# M633.net
KiCad netlist of a schematic drawn in EAGLE
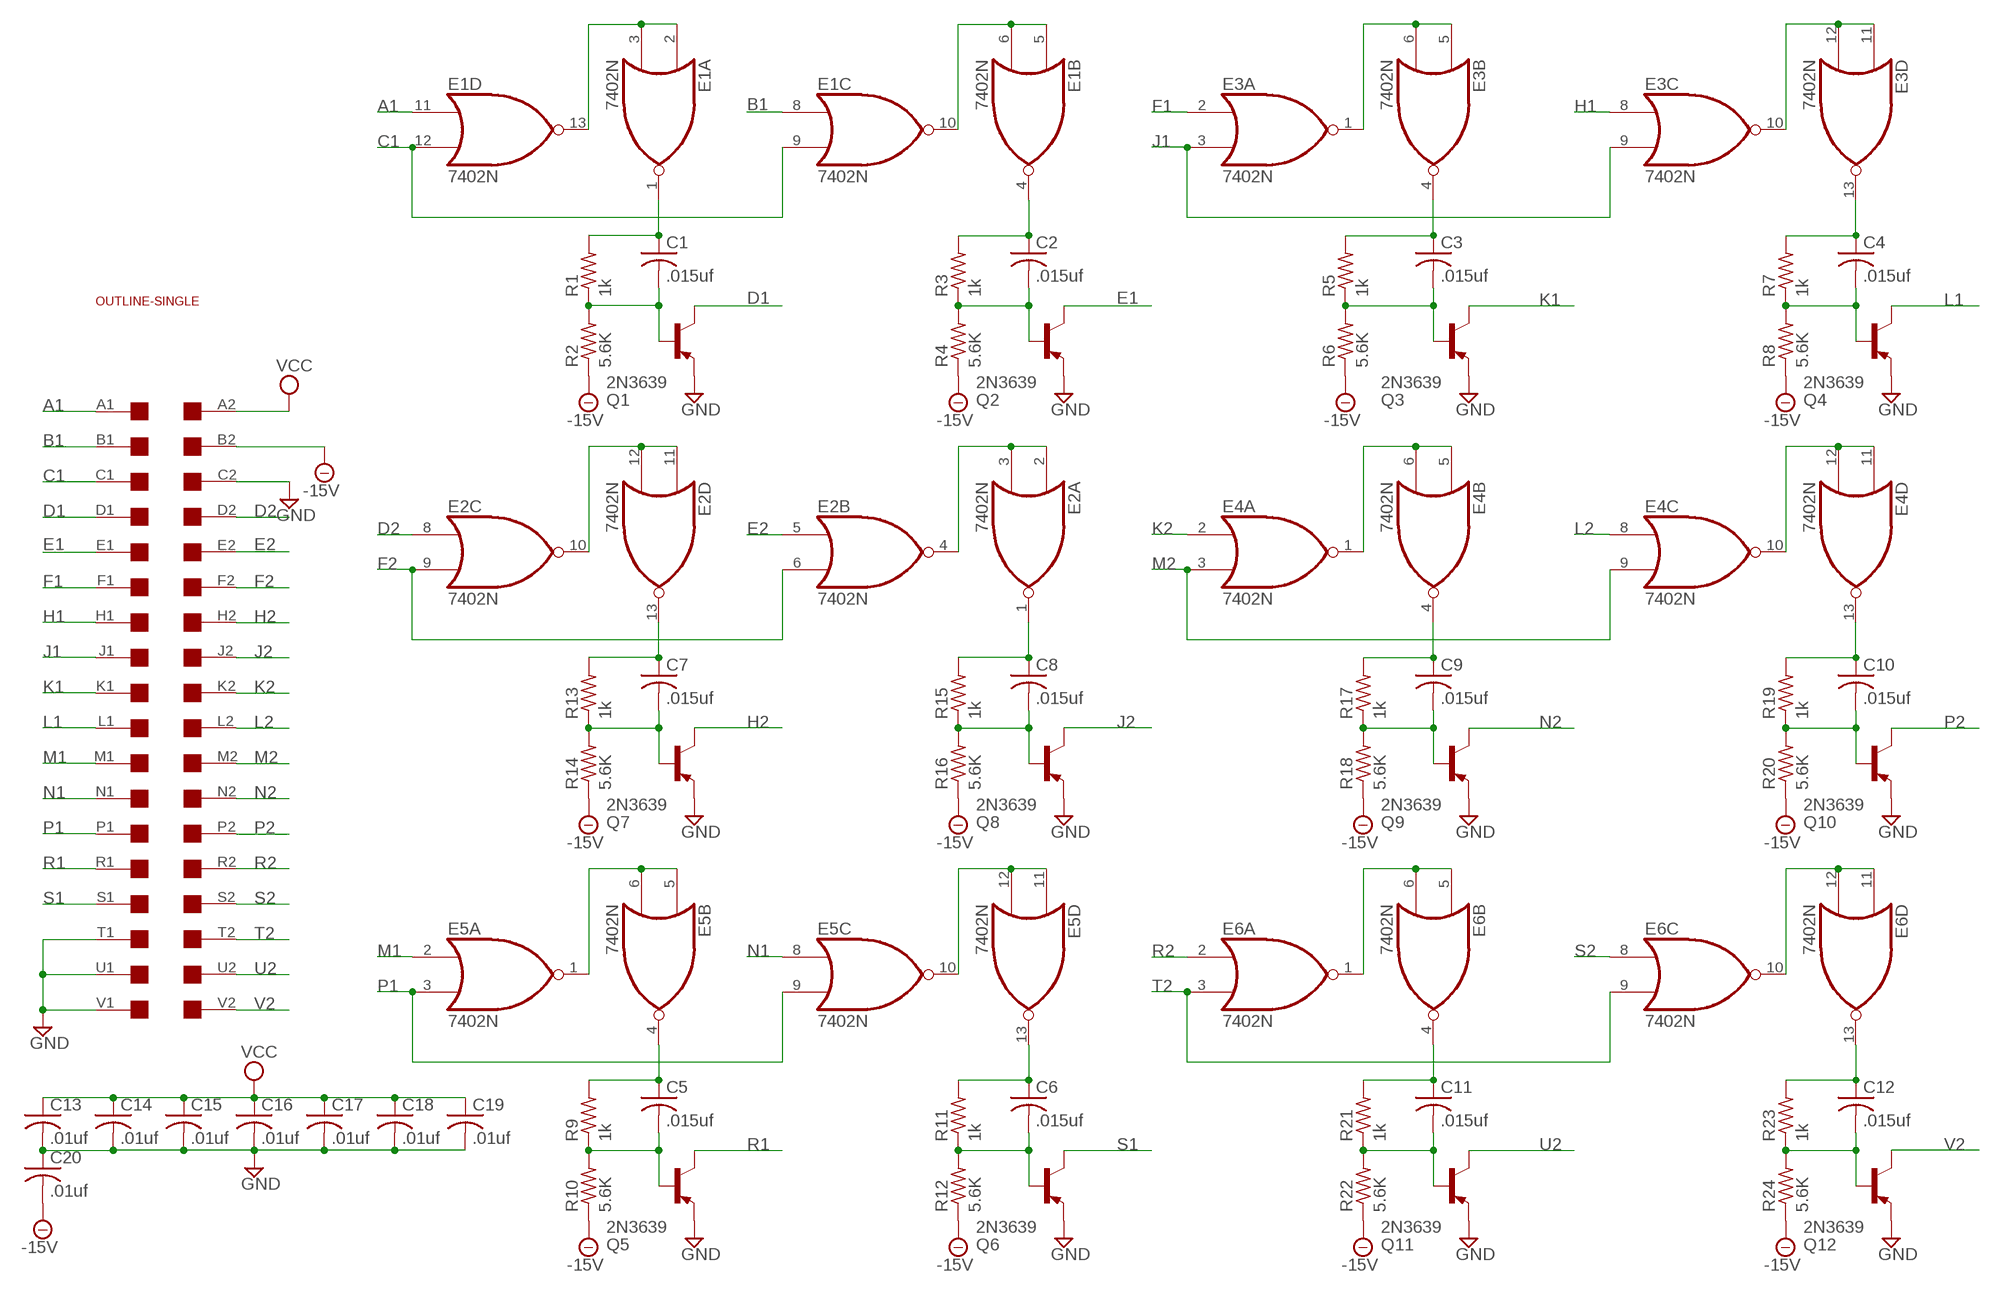
[diagram p0: schematic, sheet 1]

(export (version "E")
  (design (tool "Eeschema 10.0.6"))
  (components
    (comp (ref "C1")
      (value ".015uf")
      (footprint "eagle-import:C050-025X075")
      (libsource (lib "eagle-import") (part "C-US050-025X075"))
    )
    (comp (ref "C2")
      (value ".015uf")
      (footprint "eagle-import:C050-025X075")
      (libsource (lib "eagle-import") (part "C-US050-025X075"))
    )
    (comp (ref "C3")
      (value ".015uf")
      (footprint "eagle-import:C050-025X075")
      (libsource (lib "eagle-import") (part "C-US050-025X075"))
    )
    (comp (ref "C4")
      (value ".015uf")
      (footprint "eagle-import:C050-025X075")
      (libsource (lib "eagle-import") (part "C-US050-025X075"))
    )
    (comp (ref "C5")
      (value ".015uf")
      (footprint "eagle-import:C050-025X075")
      (libsource (lib "eagle-import") (part "C-US050-025X075"))
    )
    (comp (ref "C6")
      (value ".015uf")
      (footprint "eagle-import:C050-025X075")
      (libsource (lib "eagle-import") (part "C-US050-025X075"))
    )
    (comp (ref "C7")
      (value ".015uf")
      (footprint "eagle-import:C050-025X075")
      (libsource (lib "eagle-import") (part "C-US050-025X075"))
    )
    (comp (ref "C8")
      (value ".015uf")
      (footprint "eagle-import:C050-025X075")
      (libsource (lib "eagle-import") (part "C-US050-025X075"))
    )
    (comp (ref "C9")
      (value ".015uf")
      (footprint "eagle-import:C050-025X075")
      (libsource (lib "eagle-import") (part "C-US050-025X075"))
    )
    (comp (ref "C10")
      (value ".015uf")
      (footprint "eagle-import:C050-025X075")
      (libsource (lib "eagle-import") (part "C-US050-025X075"))
    )
    (comp (ref "C11")
      (value ".015uf")
      (footprint "eagle-import:C050-025X075")
      (libsource (lib "eagle-import") (part "C-US050-025X075"))
    )
    (comp (ref "C12")
      (value ".015uf")
      (footprint "eagle-import:C050-025X075")
      (libsource (lib "eagle-import") (part "C-US050-025X075"))
    )
    (comp (ref "C13")
      (value ".01uf")
      (footprint "eagle-import:C050-025X075")
      (libsource (lib "eagle-import") (part "C-US050-025X075"))
    )
    (comp (ref "C14")
      (value ".01uf")
      (footprint "eagle-import:C050-025X075")
      (libsource (lib "eagle-import") (part "C-US050-025X075"))
    )
    (comp (ref "C15")
      (value ".01uf")
      (footprint "eagle-import:C050-025X075")
      (libsource (lib "eagle-import") (part "C-US050-025X075"))
    )
    (comp (ref "C16")
      (value ".01uf")
      (footprint "eagle-import:C050-025X075")
      (libsource (lib "eagle-import") (part "C-US050-025X075"))
    )
    (comp (ref "C17")
      (value ".01uf")
      (footprint "eagle-import:C050-025X075")
      (libsource (lib "eagle-import") (part "C-US050-025X075"))
    )
    (comp (ref "C18")
      (value ".01uf")
      (footprint "eagle-import:C050-025X075")
      (libsource (lib "eagle-import") (part "C-US050-025X075"))
    )
    (comp (ref "C19")
      (value ".01uf")
      (footprint "eagle-import:C050-025X075")
      (libsource (lib "eagle-import") (part "C-US050-025X075"))
    )
    (comp (ref "C20")
      (value ".01uf")
      (footprint "eagle-import:C050-025X075")
      (libsource (lib "eagle-import") (part "C-US050-025X075"))
    )
    (comp (ref "E1")
      (value "7402N")
      (footprint "eagle-import:DIL14")
      (libsource (lib "eagle-import") (part "7402N"))
    )
    (comp (ref "E2")
      (value "7402N")
      (footprint "eagle-import:DIL14")
      (libsource (lib "eagle-import") (part "7402N"))
    )
    (comp (ref "E3")
      (value "7402N")
      (footprint "eagle-import:DIL14")
      (libsource (lib "eagle-import") (part "7402N"))
    )
    (comp (ref "E4")
      (value "7402N")
      (footprint "eagle-import:DIL14")
      (libsource (lib "eagle-import") (part "7402N"))
    )
    (comp (ref "E5")
      (value "7402N")
      (footprint "eagle-import:DIL14")
      (libsource (lib "eagle-import") (part "7402N"))
    )
    (comp (ref "E6")
      (value "7402N")
      (footprint "eagle-import:DIL14")
      (libsource (lib "eagle-import") (part "7402N"))
    )
    (comp (ref "Q1")
      (value "2N3639")
      (footprint "eagle-import:TO39")
      (libsource (lib "eagle-import") (part "2N5415"))
    )
    (comp (ref "Q2")
      (value "2N3639")
      (footprint "eagle-import:TO39")
      (libsource (lib "eagle-import") (part "2N5415"))
    )
    (comp (ref "Q3")
      (value "2N3639")
      (footprint "eagle-import:TO39")
      (libsource (lib "eagle-import") (part "2N5415"))
    )
    (comp (ref "Q4")
      (value "2N3639")
      (footprint "eagle-import:TO39")
      (libsource (lib "eagle-import") (part "2N5415"))
    )
    (comp (ref "Q5")
      (value "2N3639")
      (footprint "eagle-import:TO39")
      (libsource (lib "eagle-import") (part "2N5415"))
    )
    (comp (ref "Q6")
      (value "2N3639")
      (footprint "eagle-import:TO39")
      (libsource (lib "eagle-import") (part "2N5415"))
    )
    (comp (ref "Q7")
      (value "2N3639")
      (footprint "eagle-import:TO39")
      (libsource (lib "eagle-import") (part "2N5415"))
    )
    (comp (ref "Q8")
      (value "2N3639")
      (footprint "eagle-import:TO39")
      (libsource (lib "eagle-import") (part "2N5415"))
    )
    (comp (ref "Q9")
      (value "2N3639")
      (footprint "eagle-import:TO39")
      (libsource (lib "eagle-import") (part "2N5415"))
    )
    (comp (ref "Q10")
      (value "2N3639")
      (footprint "eagle-import:TO39")
      (libsource (lib "eagle-import") (part "2N5415"))
    )
    (comp (ref "Q11")
      (value "2N3639")
      (footprint "eagle-import:TO39")
      (libsource (lib "eagle-import") (part "2N5415"))
    )
    (comp (ref "Q12")
      (value "2N3639")
      (footprint "eagle-import:TO39")
      (libsource (lib "eagle-import") (part "2N5415"))
    )
    (comp (ref "R1")
      (value "1k")
      (footprint "eagle-import:0207_10")
      (libsource (lib "eagle-import") (part "R-US_0207/10"))
    )
    (comp (ref "R2")
      (value "5.6K")
      (footprint "eagle-import:0207_10")
      (libsource (lib "eagle-import") (part "R-US_0207/10"))
    )
    (comp (ref "R3")
      (value "1k")
      (footprint "eagle-import:0207_10")
      (libsource (lib "eagle-import") (part "R-US_0207/10"))
    )
    (comp (ref "R4")
      (value "5.6K")
      (footprint "eagle-import:0207_10")
      (libsource (lib "eagle-import") (part "R-US_0207/10"))
    )
    (comp (ref "R5")
      (value "1k")
      (footprint "eagle-import:0207_10")
      (libsource (lib "eagle-import") (part "R-US_0207/10"))
    )
    (comp (ref "R6")
      (value "5.6K")
      (footprint "eagle-import:0207_10")
      (libsource (lib "eagle-import") (part "R-US_0207/10"))
    )
    (comp (ref "R7")
      (value "1k")
      (footprint "eagle-import:0207_10")
      (libsource (lib "eagle-import") (part "R-US_0207/10"))
    )
    (comp (ref "R8")
      (value "5.6K")
      (footprint "eagle-import:0207_10")
      (libsource (lib "eagle-import") (part "R-US_0207/10"))
    )
    (comp (ref "R9")
      (value "1k")
      (footprint "eagle-import:0207_10")
      (libsource (lib "eagle-import") (part "R-US_0207/10"))
    )
    (comp (ref "R10")
      (value "5.6K")
      (footprint "eagle-import:0207_10")
      (libsource (lib "eagle-import") (part "R-US_0207/10"))
    )
    (comp (ref "R11")
      (value "1k")
      (footprint "eagle-import:0207_10")
      (libsource (lib "eagle-import") (part "R-US_0207/10"))
    )
    (comp (ref "R12")
      (value "5.6K")
      (footprint "eagle-import:0207_10")
      (libsource (lib "eagle-import") (part "R-US_0207/10"))
    )
    (comp (ref "R13")
      (value "1k")
      (footprint "eagle-import:0207_10")
      (libsource (lib "eagle-import") (part "R-US_0207/10"))
    )
    (comp (ref "R14")
      (value "5.6K")
      (footprint "eagle-import:0207_10")
      (libsource (lib "eagle-import") (part "R-US_0207/10"))
    )
    (comp (ref "R15")
      (value "1k")
      (footprint "eagle-import:0207_10")
      (libsource (lib "eagle-import") (part "R-US_0207/10"))
    )
    (comp (ref "R16")
      (value "5.6K")
      (footprint "eagle-import:0207_10")
      (libsource (lib "eagle-import") (part "R-US_0207/10"))
    )
    (comp (ref "R17")
      (value "1k")
      (footprint "eagle-import:0207_10")
      (libsource (lib "eagle-import") (part "R-US_0207/10"))
    )
    (comp (ref "R18")
      (value "5.6K")
      (footprint "eagle-import:0207_10")
      (libsource (lib "eagle-import") (part "R-US_0207/10"))
    )
    (comp (ref "R19")
      (value "1k")
      (footprint "eagle-import:0207_10")
      (libsource (lib "eagle-import") (part "R-US_0207/10"))
    )
    (comp (ref "R20")
      (value "5.6K")
      (footprint "eagle-import:0207_10")
      (libsource (lib "eagle-import") (part "R-US_0207/10"))
    )
    (comp (ref "R21")
      (value "1k")
      (footprint "eagle-import:0207_10")
      (libsource (lib "eagle-import") (part "R-US_0207/10"))
    )
    (comp (ref "R22")
      (value "5.6K")
      (footprint "eagle-import:0207_10")
      (libsource (lib "eagle-import") (part "R-US_0207/10"))
    )
    (comp (ref "R23")
      (value "1k")
      (footprint "eagle-import:0207_10")
      (libsource (lib "eagle-import") (part "R-US_0207/10"))
    )
    (comp (ref "R24")
      (value "5.6K")
      (footprint "eagle-import:0207_10")
      (libsource (lib "eagle-import") (part "R-US_0207/10"))
    )
    (comp (ref "U$1")
      (value "SINGLE")
      (footprint "eagle-import:EDGE-CON2")
      (libsource (lib "eagle-import") (part "SINGLE"))
    )
    (comp (ref "U$2")
      (value "OUTLINE-SINGLE")
      (footprint "eagle-import:SINGLE")
      (libsource (lib "eagle-import") (part "OUTLINE-SINGLE"))
    )
  )
  (nets
    (net (code "1") (name "-15V") (class "Default")
      (node (ref "C20") (pin "2") (pinfunction "2_2") (pintype "passive"))
      (node (ref "R10") (pin "1") (pinfunction "1_1") (pintype "passive"))
      (node (ref "R12") (pin "1") (pinfunction "1_1") (pintype "passive"))
      (node (ref "R14") (pin "1") (pinfunction "1_1") (pintype "passive"))
      (node (ref "R16") (pin "1") (pinfunction "1_1") (pintype "passive"))
      (node (ref "R18") (pin "1") (pinfunction "1_1") (pintype "passive"))
      (node (ref "R2") (pin "1") (pinfunction "1_1") (pintype "passive"))
      (node (ref "R20") (pin "1") (pinfunction "1_1") (pintype "passive"))
      (node (ref "R22") (pin "1") (pinfunction "1_1") (pintype "passive"))
      (node (ref "R24") (pin "1") (pinfunction "1_1") (pintype "passive"))
      (node (ref "R4") (pin "1") (pinfunction "1_1") (pintype "passive"))
      (node (ref "R6") (pin "1") (pinfunction "1_1") (pintype "passive"))
      (node (ref "R8") (pin "1") (pinfunction "1_1") (pintype "passive"))
      (node (ref "U$1") (pin "B2") (pinfunction "1_B2") (pintype "bidirectional"))
    )
    (net (code "2") (name "/A1") (class "Default")
      (node (ref "E1") (pin "11") (pinfunction "I0_11") (pintype "input"))
      (node (ref "U$1") (pin "A1") (pinfunction "1_A1") (pintype "bidirectional"))
    )
    (net (code "3") (name "/B1") (class "Default")
      (node (ref "E1") (pin "8") (pinfunction "I0_8") (pintype "input"))
      (node (ref "U$1") (pin "B1") (pinfunction "1_B1") (pintype "bidirectional"))
    )
    (net (code "4") (name "/C1") (class "Default")
      (node (ref "E1") (pin "12") (pinfunction "I1_12") (pintype "input"))
      (node (ref "E1") (pin "9") (pinfunction "I1_9") (pintype "input"))
      (node (ref "U$1") (pin "C1") (pinfunction "1_C1") (pintype "bidirectional"))
    )
    (net (code "5") (name "/D1") (class "Default")
      (node (ref "Q1") (pin "3") (pinfunction "C_3") (pintype "passive"))
      (node (ref "U$1") (pin "D1") (pinfunction "1_D1") (pintype "bidirectional"))
    )
    (net (code "6") (name "/D2") (class "Default")
      (node (ref "E2") (pin "8") (pinfunction "I0_8") (pintype "input"))
      (node (ref "U$1") (pin "D2") (pinfunction "1_D2") (pintype "bidirectional"))
    )
    (net (code "7") (name "/E1") (class "Default")
      (node (ref "Q2") (pin "3") (pinfunction "C_3") (pintype "passive"))
      (node (ref "U$1") (pin "E1") (pinfunction "1_E1") (pintype "bidirectional"))
    )
    (net (code "8") (name "/E2") (class "Default")
      (node (ref "E2") (pin "5") (pinfunction "I0_5") (pintype "input"))
      (node (ref "U$1") (pin "E2") (pinfunction "1_E2") (pintype "bidirectional"))
    )
    (net (code "9") (name "/F1") (class "Default")
      (node (ref "E3") (pin "2") (pinfunction "I0_2") (pintype "input"))
      (node (ref "U$1") (pin "F1") (pinfunction "1_F1") (pintype "bidirectional"))
    )
    (net (code "10") (name "/F2") (class "Default")
      (node (ref "E2") (pin "6") (pinfunction "I1_6") (pintype "input"))
      (node (ref "E2") (pin "9") (pinfunction "I1_9") (pintype "input"))
      (node (ref "U$1") (pin "F2") (pinfunction "1_F2") (pintype "bidirectional"))
    )
    (net (code "11") (name "/H1") (class "Default")
      (node (ref "E3") (pin "8") (pinfunction "I0_8") (pintype "input"))
      (node (ref "U$1") (pin "H1") (pinfunction "1_H1") (pintype "bidirectional"))
    )
    (net (code "12") (name "/H2") (class "Default")
      (node (ref "Q7") (pin "3") (pinfunction "C_3") (pintype "passive"))
      (node (ref "U$1") (pin "H2") (pinfunction "1_H2") (pintype "bidirectional"))
    )
    (net (code "13") (name "/J1") (class "Default")
      (node (ref "E3") (pin "3") (pinfunction "I1_3") (pintype "input"))
      (node (ref "E3") (pin "9") (pinfunction "I1_9") (pintype "input"))
      (node (ref "U$1") (pin "J1") (pinfunction "1_J1") (pintype "bidirectional"))
    )
    (net (code "14") (name "/J2") (class "Default")
      (node (ref "Q8") (pin "3") (pinfunction "C_3") (pintype "passive"))
      (node (ref "U$1") (pin "J2") (pinfunction "1_J2") (pintype "bidirectional"))
    )
    (net (code "15") (name "/K1") (class "Default")
      (node (ref "Q3") (pin "3") (pinfunction "C_3") (pintype "passive"))
      (node (ref "U$1") (pin "K1") (pinfunction "1_K1") (pintype "bidirectional"))
    )
    (net (code "16") (name "/K2") (class "Default")
      (node (ref "E4") (pin "2") (pinfunction "I0_2") (pintype "input"))
      (node (ref "U$1") (pin "K2") (pinfunction "1_K2") (pintype "bidirectional"))
    )
    (net (code "17") (name "/L1") (class "Default")
      (node (ref "Q4") (pin "3") (pinfunction "C_3") (pintype "passive"))
      (node (ref "U$1") (pin "L1") (pinfunction "1_L1") (pintype "bidirectional"))
    )
    (net (code "18") (name "/L2") (class "Default")
      (node (ref "E4") (pin "8") (pinfunction "I0_8") (pintype "input"))
      (node (ref "U$1") (pin "L2") (pinfunction "1_L2") (pintype "bidirectional"))
    )
    (net (code "19") (name "/M1") (class "Default")
      (node (ref "E5") (pin "2") (pinfunction "I0_2") (pintype "input"))
      (node (ref "U$1") (pin "M1") (pinfunction "1_M1") (pintype "bidirectional"))
    )
    (net (code "20") (name "/M2") (class "Default")
      (node (ref "E4") (pin "3") (pinfunction "I1_3") (pintype "input"))
      (node (ref "E4") (pin "9") (pinfunction "I1_9") (pintype "input"))
      (node (ref "U$1") (pin "M2") (pinfunction "1_M2") (pintype "bidirectional"))
    )
    (net (code "21") (name "/N1") (class "Default")
      (node (ref "E5") (pin "8") (pinfunction "I0_8") (pintype "input"))
      (node (ref "U$1") (pin "N1") (pinfunction "1_N1") (pintype "bidirectional"))
    )
    (net (code "22") (name "/N2") (class "Default")
      (node (ref "Q9") (pin "3") (pinfunction "C_3") (pintype "passive"))
      (node (ref "U$1") (pin "N2") (pinfunction "1_N2") (pintype "bidirectional"))
    )
    (net (code "23") (name "/P1") (class "Default")
      (node (ref "E5") (pin "3") (pinfunction "I1_3") (pintype "input"))
      (node (ref "E5") (pin "9") (pinfunction "I1_9") (pintype "input"))
      (node (ref "U$1") (pin "P1") (pinfunction "1_P1") (pintype "bidirectional"))
    )
    (net (code "24") (name "/P2") (class "Default")
      (node (ref "Q10") (pin "3") (pinfunction "C_3") (pintype "passive"))
      (node (ref "U$1") (pin "P2") (pinfunction "1_P2") (pintype "bidirectional"))
    )
    (net (code "25") (name "/R1") (class "Default")
      (node (ref "Q5") (pin "3") (pinfunction "C_3") (pintype "passive"))
      (node (ref "U$1") (pin "R1") (pinfunction "1_R1") (pintype "bidirectional"))
    )
    (net (code "26") (name "/R2") (class "Default")
      (node (ref "E6") (pin "2") (pinfunction "I0_2") (pintype "input"))
      (node (ref "U$1") (pin "R2") (pinfunction "1_R2") (pintype "bidirectional"))
    )
    (net (code "27") (name "/S1") (class "Default")
      (node (ref "Q6") (pin "3") (pinfunction "C_3") (pintype "passive"))
      (node (ref "U$1") (pin "S1") (pinfunction "1_S1") (pintype "bidirectional"))
    )
    (net (code "28") (name "/S2") (class "Default")
      (node (ref "E6") (pin "8") (pinfunction "I0_8") (pintype "input"))
      (node (ref "U$1") (pin "S2") (pinfunction "1_S2") (pintype "bidirectional"))
    )
    (net (code "29") (name "/T2") (class "Default")
      (node (ref "E6") (pin "3") (pinfunction "I1_3") (pintype "input"))
      (node (ref "E6") (pin "9") (pinfunction "I1_9") (pintype "input"))
      (node (ref "U$1") (pin "T2") (pinfunction "1_T2") (pintype "bidirectional"))
    )
    (net (code "30") (name "/U2") (class "Default")
      (node (ref "Q11") (pin "3") (pinfunction "C_3") (pintype "passive"))
      (node (ref "U$1") (pin "U2") (pinfunction "1_U2") (pintype "bidirectional"))
    )
    (net (code "31") (name "/V2") (class "Default")
      (node (ref "Q12") (pin "3") (pinfunction "C_3") (pintype "passive"))
      (node (ref "U$1") (pin "V2") (pinfunction "1_V2") (pintype "bidirectional"))
    )
    (net (code "32") (name "GND") (class "Default")
      (node (ref "C13") (pin "2") (pinfunction "2_2") (pintype "passive"))
      (node (ref "C14") (pin "2") (pinfunction "2_2") (pintype "passive"))
      (node (ref "C15") (pin "2") (pinfunction "2_2") (pintype "passive"))
      (node (ref "C16") (pin "2") (pinfunction "2_2") (pintype "passive"))
      (node (ref "C17") (pin "2") (pinfunction "2_2") (pintype "passive"))
      (node (ref "C18") (pin "2") (pinfunction "2_2") (pintype "passive"))
      (node (ref "C19") (pin "2") (pinfunction "2_2") (pintype "passive"))
      (node (ref "C20") (pin "1") (pinfunction "1_1") (pintype "passive"))
      (node (ref "Q1") (pin "1") (pinfunction "E_1") (pintype "passive"))
      (node (ref "Q10") (pin "1") (pinfunction "E_1") (pintype "passive"))
      (node (ref "Q11") (pin "1") (pinfunction "E_1") (pintype "passive"))
      (node (ref "Q12") (pin "1") (pinfunction "E_1") (pintype "passive"))
      (node (ref "Q2") (pin "1") (pinfunction "E_1") (pintype "passive"))
      (node (ref "Q3") (pin "1") (pinfunction "E_1") (pintype "passive"))
      (node (ref "Q4") (pin "1") (pinfunction "E_1") (pintype "passive"))
      (node (ref "Q5") (pin "1") (pinfunction "E_1") (pintype "passive"))
      (node (ref "Q6") (pin "1") (pinfunction "E_1") (pintype "passive"))
      (node (ref "Q7") (pin "1") (pinfunction "E_1") (pintype "passive"))
      (node (ref "Q8") (pin "1") (pinfunction "E_1") (pintype "passive"))
      (node (ref "Q9") (pin "1") (pinfunction "E_1") (pintype "passive"))
      (node (ref "U$1") (pin "C2") (pinfunction "1_C2") (pintype "bidirectional"))
      (node (ref "U$1") (pin "T1") (pinfunction "1_T1") (pintype "bidirectional"))
      (node (ref "U$1") (pin "U1") (pinfunction "1_U1") (pintype "bidirectional"))
      (node (ref "U$1") (pin "V1") (pinfunction "1_V1") (pintype "bidirectional"))
    )
    (net (code "33") (name "Net-(E1A-I0)") (class "Default")
      (node (ref "E1") (pin "13") (pinfunction "O_13") (pintype "output"))
      (node (ref "E1") (pin "2") (pinfunction "I0_2") (pintype "input"))
      (node (ref "E1") (pin "3") (pinfunction "I1_3") (pintype "input"))
    )
    (net (code "34") (name "Net-(E1A-O)") (class "Default")
      (node (ref "C1") (pin "1") (pinfunction "1_1") (pintype "passive"))
      (node (ref "E1") (pin "1") (pinfunction "O_1") (pintype "output"))
      (node (ref "R1") (pin "2") (pinfunction "2_2") (pintype "passive"))
    )
    (net (code "35") (name "Net-(E1B-I0)") (class "Default")
      (node (ref "E1") (pin "10") (pinfunction "O_10") (pintype "output"))
      (node (ref "E1") (pin "5") (pinfunction "I0_5") (pintype "input"))
      (node (ref "E1") (pin "6") (pinfunction "I1_6") (pintype "input"))
    )
    (net (code "36") (name "Net-(E1B-O)") (class "Default")
      (node (ref "C2") (pin "1") (pinfunction "1_1") (pintype "passive"))
      (node (ref "E1") (pin "4") (pinfunction "O_4") (pintype "output"))
      (node (ref "R3") (pin "2") (pinfunction "2_2") (pintype "passive"))
    )
    (net (code "37") (name "Net-(E2A-I0)") (class "Default")
      (node (ref "E2") (pin "2") (pinfunction "I0_2") (pintype "input"))
      (node (ref "E2") (pin "3") (pinfunction "I1_3") (pintype "input"))
      (node (ref "E2") (pin "4") (pinfunction "O_4") (pintype "output"))
    )
    (net (code "38") (name "Net-(E2A-O)") (class "Default")
      (node (ref "C8") (pin "1") (pinfunction "1_1") (pintype "passive"))
      (node (ref "E2") (pin "1") (pinfunction "O_1") (pintype "output"))
      (node (ref "R15") (pin "2") (pinfunction "2_2") (pintype "passive"))
    )
    (net (code "39") (name "Net-(E2C-O)") (class "Default")
      (node (ref "E2") (pin "10") (pinfunction "O_10") (pintype "output"))
      (node (ref "E2") (pin "11") (pinfunction "I0_11") (pintype "input"))
      (node (ref "E2") (pin "12") (pinfunction "I1_12") (pintype "input"))
    )
    (net (code "40") (name "Net-(E2D-O)") (class "Default")
      (node (ref "C7") (pin "1") (pinfunction "1_1") (pintype "passive"))
      (node (ref "E2") (pin "13") (pinfunction "O_13") (pintype "output"))
      (node (ref "R13") (pin "2") (pinfunction "2_2") (pintype "passive"))
    )
    (net (code "41") (name "Net-(E3A-O)") (class "Default")
      (node (ref "E3") (pin "1") (pinfunction "O_1") (pintype "output"))
      (node (ref "E3") (pin "5") (pinfunction "I0_5") (pintype "input"))
      (node (ref "E3") (pin "6") (pinfunction "I1_6") (pintype "input"))
    )
    (net (code "42") (name "Net-(E3B-O)") (class "Default")
      (node (ref "C3") (pin "1") (pinfunction "1_1") (pintype "passive"))
      (node (ref "E3") (pin "4") (pinfunction "O_4") (pintype "output"))
      (node (ref "R5") (pin "2") (pinfunction "2_2") (pintype "passive"))
    )
    (net (code "43") (name "Net-(E3C-O)") (class "Default")
      (node (ref "E3") (pin "10") (pinfunction "O_10") (pintype "output"))
      (node (ref "E3") (pin "11") (pinfunction "I0_11") (pintype "input"))
      (node (ref "E3") (pin "12") (pinfunction "I1_12") (pintype "input"))
    )
    (net (code "44") (name "Net-(E3D-O)") (class "Default")
      (node (ref "C4") (pin "1") (pinfunction "1_1") (pintype "passive"))
      (node (ref "E3") (pin "13") (pinfunction "O_13") (pintype "output"))
      (node (ref "R7") (pin "2") (pinfunction "2_2") (pintype "passive"))
    )
    (net (code "45") (name "Net-(E4A-O)") (class "Default")
      (node (ref "E4") (pin "1") (pinfunction "O_1") (pintype "output"))
      (node (ref "E4") (pin "5") (pinfunction "I0_5") (pintype "input"))
      (node (ref "E4") (pin "6") (pinfunction "I1_6") (pintype "input"))
    )
    (net (code "46") (name "Net-(E4B-O)") (class "Default")
      (node (ref "C9") (pin "1") (pinfunction "1_1") (pintype "passive"))
      (node (ref "E4") (pin "4") (pinfunction "O_4") (pintype "output"))
      (node (ref "R17") (pin "2") (pinfunction "2_2") (pintype "passive"))
    )
    (net (code "47") (name "Net-(E4C-O)") (class "Default")
      (node (ref "E4") (pin "10") (pinfunction "O_10") (pintype "output"))
      (node (ref "E4") (pin "11") (pinfunction "I0_11") (pintype "input"))
      (node (ref "E4") (pin "12") (pinfunction "I1_12") (pintype "input"))
    )
    (net (code "48") (name "Net-(E4D-O)") (class "Default")
      (node (ref "C10") (pin "1") (pinfunction "1_1") (pintype "passive"))
      (node (ref "E4") (pin "13") (pinfunction "O_13") (pintype "output"))
      (node (ref "R19") (pin "2") (pinfunction "2_2") (pintype "passive"))
    )
    (net (code "49") (name "Net-(E5A-O)") (class "Default")
      (node (ref "E5") (pin "1") (pinfunction "O_1") (pintype "output"))
      (node (ref "E5") (pin "5") (pinfunction "I0_5") (pintype "input"))
      (node (ref "E5") (pin "6") (pinfunction "I1_6") (pintype "input"))
    )
    (net (code "50") (name "Net-(E5B-O)") (class "Default")
      (node (ref "C5") (pin "1") (pinfunction "1_1") (pintype "passive"))
      (node (ref "E5") (pin "4") (pinfunction "O_4") (pintype "output"))
      (node (ref "R9") (pin "2") (pinfunction "2_2") (pintype "passive"))
    )
    (net (code "51") (name "Net-(E5C-O)") (class "Default")
      (node (ref "E5") (pin "10") (pinfunction "O_10") (pintype "output"))
      (node (ref "E5") (pin "11") (pinfunction "I0_11") (pintype "input"))
      (node (ref "E5") (pin "12") (pinfunction "I1_12") (pintype "input"))
    )
    (net (code "52") (name "Net-(E5D-O)") (class "Default")
      (node (ref "C6") (pin "1") (pinfunction "1_1") (pintype "passive"))
      (node (ref "E5") (pin "13") (pinfunction "O_13") (pintype "output"))
      (node (ref "R11") (pin "2") (pinfunction "2_2") (pintype "passive"))
    )
    (net (code "53") (name "Net-(E6A-O)") (class "Default")
      (node (ref "E6") (pin "1") (pinfunction "O_1") (pintype "output"))
      (node (ref "E6") (pin "5") (pinfunction "I0_5") (pintype "input"))
      (node (ref "E6") (pin "6") (pinfunction "I1_6") (pintype "input"))
    )
    (net (code "54") (name "Net-(E6B-O)") (class "Default")
      (node (ref "C11") (pin "1") (pinfunction "1_1") (pintype "passive"))
      (node (ref "E6") (pin "4") (pinfunction "O_4") (pintype "output"))
      (node (ref "R21") (pin "2") (pinfunction "2_2") (pintype "passive"))
    )
    (net (code "55") (name "Net-(E6C-O)") (class "Default")
      (node (ref "E6") (pin "10") (pinfunction "O_10") (pintype "output"))
      (node (ref "E6") (pin "11") (pinfunction "I0_11") (pintype "input"))
      (node (ref "E6") (pin "12") (pinfunction "I1_12") (pintype "input"))
    )
    (net (code "56") (name "Net-(E6D-O)") (class "Default")
      (node (ref "C12") (pin "1") (pinfunction "1_1") (pintype "passive"))
      (node (ref "E6") (pin "13") (pinfunction "O_13") (pintype "output"))
      (node (ref "R23") (pin "2") (pinfunction "2_2") (pintype "passive"))
    )
    (net (code "57") (name "Net-(Q1-B)") (class "Default")
      (node (ref "C1") (pin "2") (pinfunction "2_2") (pintype "passive"))
      (node (ref "Q1") (pin "2") (pinfunction "B_2") (pintype "passive"))
      (node (ref "R1") (pin "1") (pinfunction "1_1") (pintype "passive"))
      (node (ref "R2") (pin "2") (pinfunction "2_2") (pintype "passive"))
    )
    (net (code "58") (name "Net-(Q2-B)") (class "Default")
      (node (ref "C2") (pin "2") (pinfunction "2_2") (pintype "passive"))
      (node (ref "Q2") (pin "2") (pinfunction "B_2") (pintype "passive"))
      (node (ref "R3") (pin "1") (pinfunction "1_1") (pintype "passive"))
      (node (ref "R4") (pin "2") (pinfunction "2_2") (pintype "passive"))
    )
    (net (code "59") (name "Net-(Q3-B)") (class "Default")
      (node (ref "C3") (pin "2") (pinfunction "2_2") (pintype "passive"))
      (node (ref "Q3") (pin "2") (pinfunction "B_2") (pintype "passive"))
      (node (ref "R5") (pin "1") (pinfunction "1_1") (pintype "passive"))
      (node (ref "R6") (pin "2") (pinfunction "2_2") (pintype "passive"))
    )
    (net (code "60") (name "Net-(Q4-B)") (class "Default")
      (node (ref "C4") (pin "2") (pinfunction "2_2") (pintype "passive"))
      (node (ref "Q4") (pin "2") (pinfunction "B_2") (pintype "passive"))
      (node (ref "R7") (pin "1") (pinfunction "1_1") (pintype "passive"))
      (node (ref "R8") (pin "2") (pinfunction "2_2") (pintype "passive"))
    )
    (net (code "61") (name "Net-(Q5-B)") (class "Default")
      (node (ref "C5") (pin "2") (pinfunction "2_2") (pintype "passive"))
      (node (ref "Q5") (pin "2") (pinfunction "B_2") (pintype "passive"))
      (node (ref "R10") (pin "2") (pinfunction "2_2") (pintype "passive"))
      (node (ref "R9") (pin "1") (pinfunction "1_1") (pintype "passive"))
    )
    (net (code "62") (name "Net-(Q6-B)") (class "Default")
      (node (ref "C6") (pin "2") (pinfunction "2_2") (pintype "passive"))
      (node (ref "Q6") (pin "2") (pinfunction "B_2") (pintype "passive"))
      (node (ref "R11") (pin "1") (pinfunction "1_1") (pintype "passive"))
      (node (ref "R12") (pin "2") (pinfunction "2_2") (pintype "passive"))
    )
    (net (code "63") (name "Net-(Q7-B)") (class "Default")
      (node (ref "C7") (pin "2") (pinfunction "2_2") (pintype "passive"))
      (node (ref "Q7") (pin "2") (pinfunction "B_2") (pintype "passive"))
      (node (ref "R13") (pin "1") (pinfunction "1_1") (pintype "passive"))
      (node (ref "R14") (pin "2") (pinfunction "2_2") (pintype "passive"))
    )
    (net (code "64") (name "Net-(Q8-B)") (class "Default")
      (node (ref "C8") (pin "2") (pinfunction "2_2") (pintype "passive"))
      (node (ref "Q8") (pin "2") (pinfunction "B_2") (pintype "passive"))
      (node (ref "R15") (pin "1") (pinfunction "1_1") (pintype "passive"))
      (node (ref "R16") (pin "2") (pinfunction "2_2") (pintype "passive"))
    )
    (net (code "65") (name "Net-(Q9-B)") (class "Default")
      (node (ref "C9") (pin "2") (pinfunction "2_2") (pintype "passive"))
      (node (ref "Q9") (pin "2") (pinfunction "B_2") (pintype "passive"))
      (node (ref "R17") (pin "1") (pinfunction "1_1") (pintype "passive"))
      (node (ref "R18") (pin "2") (pinfunction "2_2") (pintype "passive"))
    )
    (net (code "66") (name "Net-(Q10-B)") (class "Default")
      (node (ref "C10") (pin "2") (pinfunction "2_2") (pintype "passive"))
      (node (ref "Q10") (pin "2") (pinfunction "B_2") (pintype "passive"))
      (node (ref "R19") (pin "1") (pinfunction "1_1") (pintype "passive"))
      (node (ref "R20") (pin "2") (pinfunction "2_2") (pintype "passive"))
    )
    (net (code "67") (name "Net-(Q11-B)") (class "Default")
      (node (ref "C11") (pin "2") (pinfunction "2_2") (pintype "passive"))
      (node (ref "Q11") (pin "2") (pinfunction "B_2") (pintype "passive"))
      (node (ref "R21") (pin "1") (pinfunction "1_1") (pintype "passive"))
      (node (ref "R22") (pin "2") (pinfunction "2_2") (pintype "passive"))
    )
    (net (code "68") (name "Net-(Q12-B)") (class "Default")
      (node (ref "C12") (pin "2") (pinfunction "2_2") (pintype "passive"))
      (node (ref "Q12") (pin "2") (pinfunction "B_2") (pintype "passive"))
      (node (ref "R23") (pin "1") (pinfunction "1_1") (pintype "passive"))
      (node (ref "R24") (pin "2") (pinfunction "2_2") (pintype "passive"))
    )
    (net (code "69") (name "VCC") (class "Default")
      (node (ref "C13") (pin "1") (pinfunction "1_1") (pintype "passive"))
      (node (ref "C14") (pin "1") (pinfunction "1_1") (pintype "passive"))
      (node (ref "C15") (pin "1") (pinfunction "1_1") (pintype "passive"))
      (node (ref "C16") (pin "1") (pinfunction "1_1") (pintype "passive"))
      (node (ref "C17") (pin "1") (pinfunction "1_1") (pintype "passive"))
      (node (ref "C18") (pin "1") (pinfunction "1_1") (pintype "passive"))
      (node (ref "C19") (pin "1") (pinfunction "1_1") (pintype "passive"))
      (node (ref "U$1") (pin "A2") (pinfunction "1_A2") (pintype "bidirectional"))
    )
  )
)
